# pca20020_sheet6_environment_sensors.net
KiCad netlist of a schematic drawn in Altium Designer
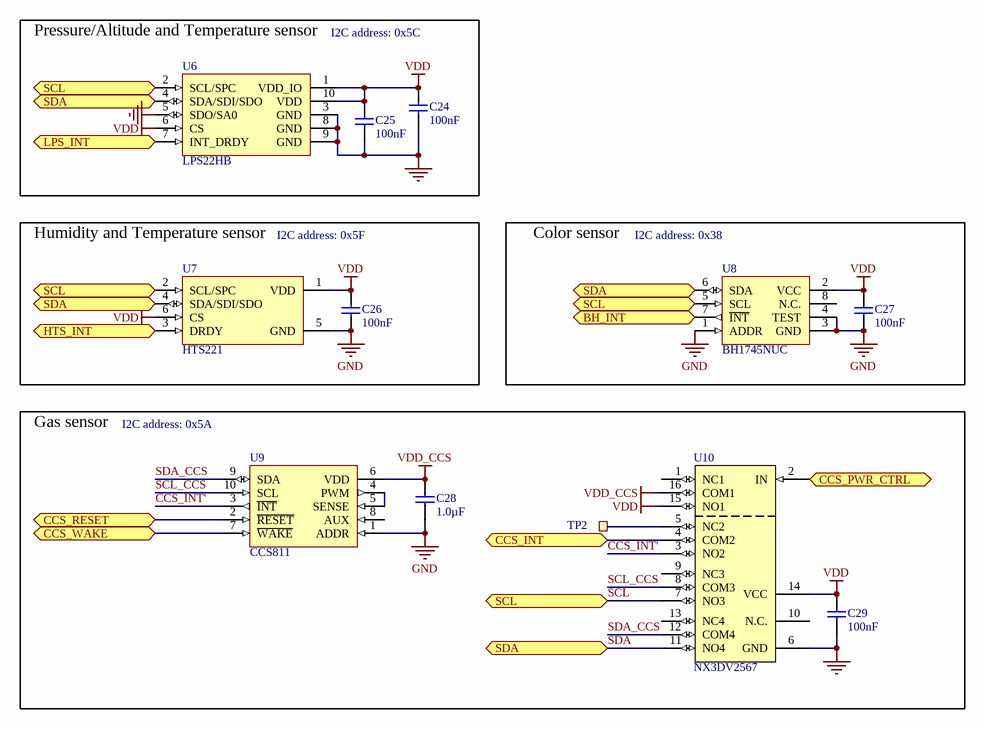
[diagram p0: pca20020_sheet6_environment_sensors.SchDoc]

(export (version "E")
  (design (tool "Eeschema 10.0.6"))
  (components
    (comp (ref "C24")
      (value "100nF")
      (footprint "CAPC1005X04L")
      (description "Capacitor, X7R, ±10%")
      (fields (field (name "PART NUMBER") "C0402-100n") (field (name "PUBLISHER") "Nordic Semiconductor"))
      (libsource (lib "Nordic Passive DB") (part "CAP"))
    )
    (comp (ref "C25")
      (value "100nF")
      (footprint "CAPC1005X04L")
      (description "Capacitor, X7R, ±10%")
      (fields (field (name "PART NUMBER") "C0402-100n") (field (name "PUBLISHER") "Nordic Semiconductor"))
      (libsource (lib "Nordic Passive DB") (part "CAP"))
    )
    (comp (ref "C26")
      (value "100nF")
      (footprint "CAPC1005X04L")
      (description "Capacitor, X7R, ±10%")
      (fields (field (name "PART NUMBER") "C0402-100n") (field (name "PUBLISHER") "Nordic Semiconductor"))
      (libsource (lib "Nordic Passive DB") (part "CAP"))
    )
    (comp (ref "C27")
      (value "100nF")
      (footprint "CAPC1005X04L")
      (description "Capacitor, X7R, ±10%")
      (fields (field (name "PART NUMBER") "C0402-100n") (field (name "PUBLISHER") "Nordic Semiconductor"))
      (libsource (lib "Nordic Passive DB") (part "CAP"))
    )
    (comp (ref "C28")
      (value "1.0µF")
      (footprint "CAPC1005X04L")
      (description "Capacitor, X5R, ±5%")
      (fields (field (name "PART NUMBER") "C0402-1µ0") (field (name "PUBLISHER") "Nordic Semiconductor"))
      (libsource (lib "Nordic Passive DB") (part "CAP"))
    )
    (comp (ref "C29")
      (value "100nF")
      (footprint "CAPC1005X04L")
      (description "Capacitor, X7R, ±10%")
      (fields (field (name "PART NUMBER") "C0402-100n") (field (name "PUBLISHER") "Nordic Semiconductor"))
      (libsource (lib "Nordic Passive DB") (part "CAP"))
    )
    (comp (ref "TP2")
      (value "TP")
      (footprint "TESTPAD-TH")
      (description "Testpoint, through hole")
      (fields (field (name "PART NUMBER") "Testpoint TH") (field (name "PUBLISHER") "Nordic Semiconductor"))
      (libsource (lib "Nordic Passive DB") (part "TESTPAD"))
    )
    (comp (ref "U6")
      (value "LPS22HB")
      (footprint "LGA50P200X200X80-10N")
      (description "MEMS nano pressure sensor: 260-1260 hPa absolute digital output barometer")
      (fields
        (field (name "MANUFACTURER") "STMicroelectronics")
        (field (name "2ND SOURCE PART NUMBER") "511-LPS22HBTR")
        (field (name "PUBLISHER") "Nordic Semiconductor")
      )
      (libsource (lib "Nordic Active DB") (part "LPS22HB"))
    )
    (comp (ref "U7")
      (value "HTS221")
      (footprint "HLGA100P200X200X100-6N")
      (description "Capacitive digital sensor for relative humidity and temperature")
      (fields
        (field (name "MANUFACTURER") "STMicroelectronics")
        (field (name "2ND SOURCE PART NUMBER") "511-HTS221TR")
        (field (name "PUBLISHER") "Nordic Semiconductor")
      )
      (libsource (lib "Nordic Active DB") (part "HTS221"))
    )
    (comp (ref "U8")
      (value "BH1745NUC")
      (footprint "WSON50P210X210X60_HS-9N")
      (description "Digital 16bit Serial Output Type Color Sensor IC")
      (fields
        (field (name "MANUFACTURER") "Rohm Semiconductor")
        (field (name "PUBLISHER") "Nordic Semiconductor")
      )
      (libsource (lib "Nordic Active DB") (part "BH1745NUC"))
    )
    (comp (ref "U9")
      (value "CCS811")
      (footprint "LGA60P270X400X110_HS-11N")
      (description "Ultra-low power digital gas sensor for monitoring indoor air quality")
      (fields
        (field (name "MANUFACTURER") "Cambridge CMOS Sensors")
        (field (name "PUBLISHER") "Nordic Semiconductor")
      )
      (libsource (lib "Nordic Active DB") (part "CCS811"))
    )
    (comp (ref "U10")
      (value "NX3DV2567")
      (footprint "XQFN40P180X260X50-16N")
      (description "Low-ohmic four-pole double-throw analog switch")
      (fields
        (field (name "PART NUMBER") "NX3DV2567GU")
        (field (name "MANUFACTURER") "NXP Semiconductors")
        (field (name "PUBLISHER") "Nordic Semiconductor")
      )
      (libsource (lib "Nordic Active DB") (part "NX3DV2567"))
    )
  )
  (nets
    (net (code "1") (name "/BH_INT") (class "Default")
      (node (ref "U8") (pin "7") (pinfunction "~{INT}_7") (pintype "output"))
    )
    (net (code "2") (name "/CCS_INT") (class "Default")
      (node (ref "U10") (pin "4") (pinfunction "COM2_4") (pintype "bidirectional"))
    )
    (net (code "3") (name "/CCS_INT'") (class "Default")
      (node (ref "U10") (pin "3") (pinfunction "NO2_3") (pintype "bidirectional"))
      (node (ref "U9") (pin "3") (pinfunction "~{INT}_3") (pintype "output"))
    )
    (net (code "4") (name "/CCS_PWR_CTRL") (class "Default")
      (node (ref "U10") (pin "2") (pinfunction "IN_2") (pintype "input"))
    )
    (net (code "5") (name "/CCS_RESET") (class "Default")
      (node (ref "U9") (pin "2") (pinfunction "~{RESET}_2") (pintype "input"))
    )
    (net (code "6") (name "/CCS_WAKE") (class "Default")
      (node (ref "U9") (pin "7") (pinfunction "~{WAKE}_7") (pintype "input"))
    )
    (net (code "7") (name "/HTS_INT") (class "Default")
      (node (ref "U7") (pin "3") (pinfunction "DRDY_3") (pintype "input"))
    )
    (net (code "8") (name "/LPS_INT") (class "Default")
      (node (ref "U6") (pin "7") (pinfunction "INT_DRDY_7") (pintype "input"))
    )
    (net (code "9") (name "/SCL") (class "Default")
      (node (ref "U10") (pin "7") (pinfunction "NO3_7") (pintype "bidirectional"))
      (node (ref "U6") (pin "2") (pinfunction "SCL/SPC_2") (pintype "input"))
      (node (ref "U7") (pin "2") (pinfunction "SCL/SPC_2") (pintype "input"))
      (node (ref "U8") (pin "5") (pinfunction "SCL_5") (pintype "input"))
    )
    (net (code "10") (name "/SCL_CCS") (class "Default")
      (node (ref "U10") (pin "8") (pinfunction "COM3_8") (pintype "bidirectional"))
      (node (ref "U9") (pin "10") (pinfunction "SCL_10") (pintype "input"))
    )
    (net (code "11") (name "/SDA") (class "Default")
      (node (ref "U10") (pin "11") (pinfunction "NO4_11") (pintype "bidirectional"))
      (node (ref "U6") (pin "4") (pinfunction "SDA/SDI/SDO_4") (pintype "bidirectional"))
      (node (ref "U7") (pin "4") (pinfunction "SDA/SDI/SDO_4") (pintype "bidirectional"))
      (node (ref "U8") (pin "6") (pinfunction "SDA_6") (pintype "bidirectional"))
    )
    (net (code "12") (name "/SDA_CCS") (class "Default")
      (node (ref "U10") (pin "12") (pinfunction "COM4_12") (pintype "bidirectional"))
      (node (ref "U9") (pin "9") (pinfunction "SDA_9") (pintype "bidirectional"))
    )
    (net (code "13") (name "GND") (class "Default")
      (node (ref "C24") (pin "1") (pinfunction "1_1") (pintype "passive"))
      (node (ref "C25") (pin "1") (pinfunction "1_1") (pintype "passive"))
      (node (ref "C26") (pin "1") (pinfunction "1_1") (pintype "passive"))
      (node (ref "C27") (pin "1") (pinfunction "1_1") (pintype "passive"))
      (node (ref "C28") (pin "1") (pinfunction "1_1") (pintype "passive"))
      (node (ref "C29") (pin "1") (pinfunction "1_1") (pintype "passive"))
      (node (ref "U10") (pin "6") (pinfunction "GND_6") (pintype "power_in"))
      (node (ref "U6") (pin "3") (pinfunction "GND_3") (pintype "power_in"))
      (node (ref "U6") (pin "5") (pinfunction "SDO/SA0_5") (pintype "bidirectional"))
      (node (ref "U6") (pin "8") (pinfunction "GND_8") (pintype "power_in"))
      (node (ref "U6") (pin "9") (pinfunction "GND_9") (pintype "power_in"))
      (node (ref "U7") (pin "5") (pinfunction "GND_5") (pintype "power_in"))
      (node (ref "U8") (pin "1") (pinfunction "ADDR_1") (pintype "input"))
      (node (ref "U8") (pin "3") (pinfunction "GND_3") (pintype "power_in"))
      (node (ref "U8") (pin "4") (pinfunction "TEST_4") (pintype "passive"))
      (node (ref "U8") (pin "9") (pinfunction "GND_9") (pintype "power_in"))
      (node (ref "U9") (pin "1") (pinfunction "ADDR_1") (pintype "input"))
      (node (ref "U9") (pin "11") (pinfunction "GND_11") (pintype "power_in"))
    )
    (net (code "14") (name "Net-(U9-PWM)") (class "Default")
      (node (ref "U9") (pin "4") (pinfunction "PWM_4") (pintype "output"))
      (node (ref "U9") (pin "5") (pinfunction "SENSE_5") (pintype "input"))
    )
    (net (code "15") (name "Net-(U10-NC2)") (class "Default")
      (node (ref "TP2") (pin "1") (pinfunction "1_1") (pintype "passive"))
      (node (ref "U10") (pin "5") (pinfunction "NC2_5") (pintype "bidirectional"))
    )
    (net (code "16") (name "VDD") (class "Default")
      (node (ref "C24") (pin "2") (pinfunction "2_2") (pintype "passive"))
      (node (ref "C25") (pin "2") (pinfunction "2_2") (pintype "passive"))
      (node (ref "C26") (pin "2") (pinfunction "2_2") (pintype "passive"))
      (node (ref "C27") (pin "2") (pinfunction "2_2") (pintype "passive"))
      (node (ref "C29") (pin "2") (pinfunction "2_2") (pintype "passive"))
      (node (ref "U10") (pin "14") (pinfunction "VCC_14") (pintype "power_in"))
      (node (ref "U10") (pin "15") (pinfunction "NO1_15") (pintype "bidirectional"))
      (node (ref "U6") (pin "1") (pinfunction "VDD_IO_1") (pintype "power_in"))
      (node (ref "U6") (pin "10") (pinfunction "VDD_10") (pintype "power_in"))
      (node (ref "U6") (pin "6") (pinfunction "CS_6") (pintype "input"))
      (node (ref "U7") (pin "1") (pinfunction "VDD_1") (pintype "power_in"))
      (node (ref "U7") (pin "6") (pinfunction "CS_6") (pintype "input"))
      (node (ref "U8") (pin "2") (pinfunction "VCC_2") (pintype "power_in"))
    )
    (net (code "17") (name "VDD_CCS") (class "Default")
      (node (ref "C28") (pin "2") (pinfunction "2_2") (pintype "passive"))
      (node (ref "U10") (pin "16") (pinfunction "COM1_16") (pintype "bidirectional"))
      (node (ref "U9") (pin "6") (pinfunction "VDD_6") (pintype "power_in"))
    )
    (net (code "18") (name "unconnected-(U8-N.C.-Pad8)") (class "Default")
      (node (ref "U8") (pin "8") (pinfunction "N.C._8") (pintype "passive"))
    )
    (net (code "19") (name "unconnected-(U9-AUX-Pad8)") (class "Default")
      (node (ref "U9") (pin "8") (pinfunction "AUX_8") (pintype "input"))
    )
    (net (code "20") (name "unconnected-(U10-N.C.-Pad10)") (class "Default")
      (node (ref "U10") (pin "10") (pinfunction "N.C._10") (pintype "passive"))
    )
    (net (code "21") (name "unconnected-(U10-NC1-Pad1)") (class "Default")
      (node (ref "U10") (pin "1") (pinfunction "NC1_1") (pintype "bidirectional"))
    )
    (net (code "22") (name "unconnected-(U10-NC3-Pad9)") (class "Default")
      (node (ref "U10") (pin "9") (pinfunction "NC3_9") (pintype "bidirectional"))
    )
    (net (code "23") (name "unconnected-(U10-NC4-Pad13)") (class "Default")
      (node (ref "U10") (pin "13") (pinfunction "NC4_13") (pintype "bidirectional"))
    )
  )
)
